# STRWHL-S02-V00-Microcontroller.net
KiCad netlist of a schematic drawn in Altium Designer
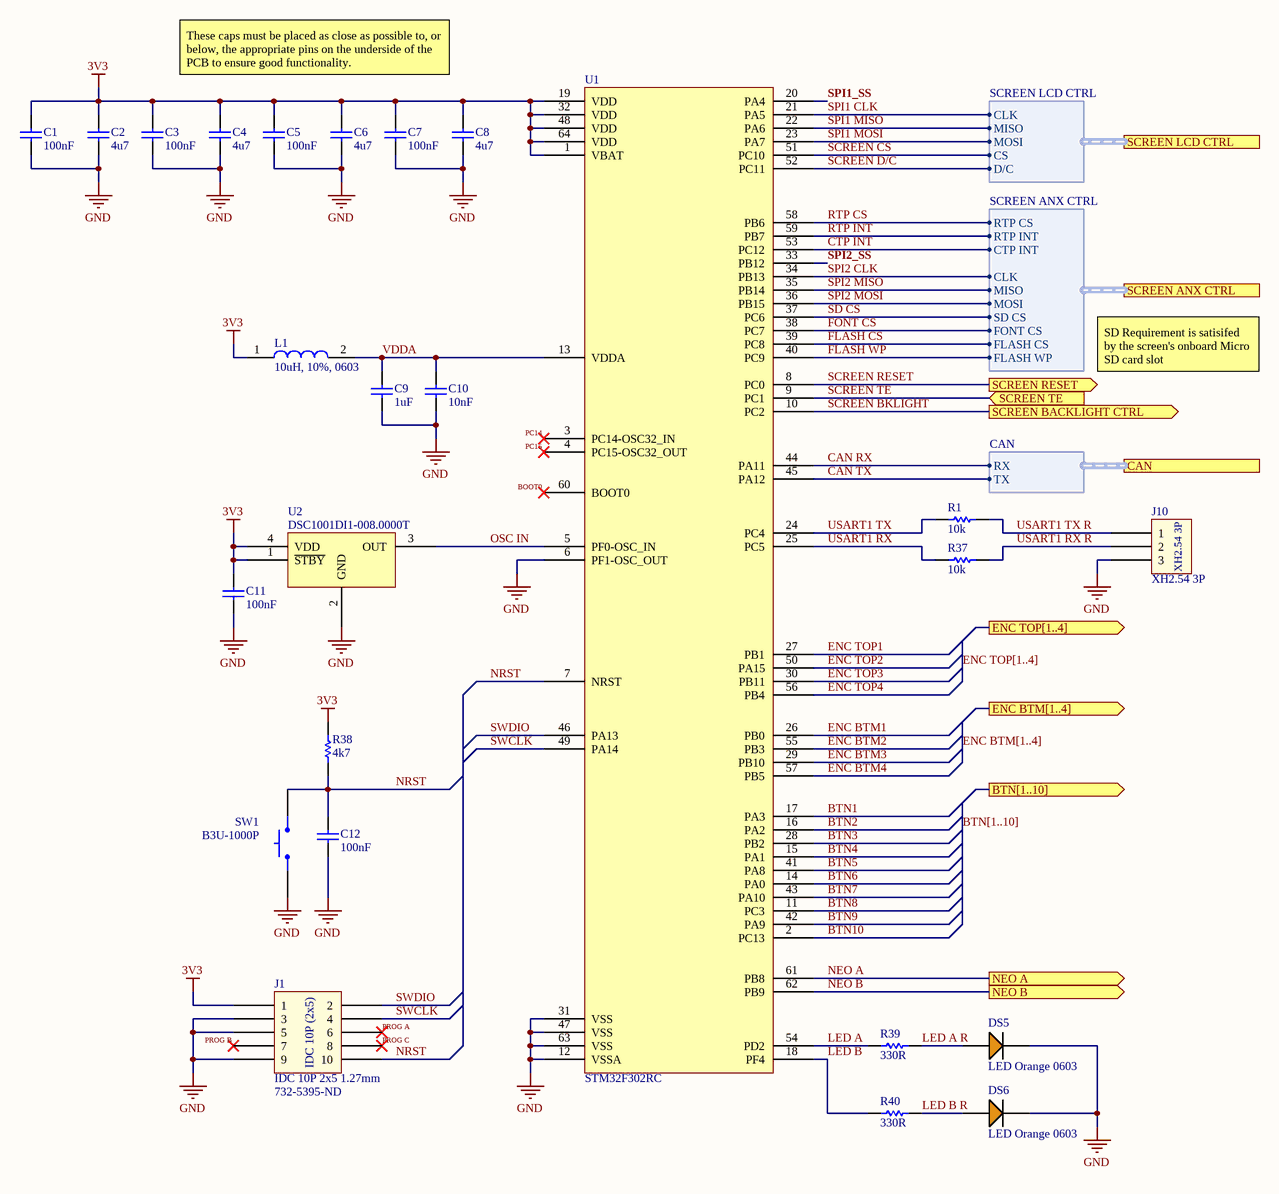
[diagram p0: STRWHL-S02-V00-Microcontroller.SchDoc]

(export (version "E")
  (design (tool "Eeschema 10.0.6"))
  (components
    (comp (ref "C1")
      (value "100nF")
      (footprint "Cap_Ceramic_0603")
      (description "Capacitor, Ceramic, SMD, 100nF, 50V, 5%, X7R, 0603")
      (libsource (lib "StandardCapacitors") (part "100nF 50V 5% X7R 0603"))
    )
    (comp (ref "C2")
      (value "4u7")
      (footprint "Cap_Ceramic_0603")
      (description "Capacitor, Ceramic, SMD, 4u7, 50V, 5%, X7R, 0603")
      (libsource (lib "StandardCapacitors") (part "4u7 50V 5% X7R 0603"))
    )
    (comp (ref "C3")
      (value "100nF")
      (footprint "Cap_Ceramic_0603")
      (description "Capacitor, Ceramic, SMD, 100nF, 50V, 5%, X7R, 0603")
      (libsource (lib "StandardCapacitors") (part "100nF 50V 5% X7R 0603"))
    )
    (comp (ref "C4")
      (value "4u7")
      (footprint "Cap_Ceramic_0603")
      (description "Capacitor, Ceramic, SMD, 4u7, 50V, 5%, X7R, 0603")
      (libsource (lib "StandardCapacitors") (part "4u7 50V 5% X7R 0603"))
    )
    (comp (ref "C5")
      (value "100nF")
      (footprint "Cap_Ceramic_0603")
      (description "Capacitor, Ceramic, SMD, 100nF, 50V, 5%, X7R, 0603")
      (libsource (lib "StandardCapacitors") (part "100nF 50V 5% X7R 0603"))
    )
    (comp (ref "C6")
      (value "4u7")
      (footprint "Cap_Ceramic_0603")
      (description "Capacitor, Ceramic, SMD, 4u7, 50V, 5%, X7R, 0603")
      (libsource (lib "StandardCapacitors") (part "4u7 50V 5% X7R 0603"))
    )
    (comp (ref "C7")
      (value "100nF")
      (footprint "Cap_Ceramic_0603")
      (description "Capacitor, Ceramic, SMD, 100nF, 50V, 5%, X7R, 0603")
      (libsource (lib "StandardCapacitors") (part "100nF 50V 5% X7R 0603"))
    )
    (comp (ref "C8")
      (value "4u7")
      (footprint "Cap_Ceramic_0603")
      (description "Capacitor, Ceramic, SMD, 4u7, 50V, 5%, X7R, 0603")
      (libsource (lib "StandardCapacitors") (part "4u7 50V 5% X7R 0603"))
    )
    (comp (ref "C9")
      (value "1uF")
      (footprint "Cap_Ceramic_0603")
      (description "Capacitor, Ceramic, SMD, 1uF, 25V, 5%, X7R, 0603")
      (libsource (lib "StandardCapacitors") (part "1uF 25V 5% X7R 0603"))
    )
    (comp (ref "C10")
      (value "10nF")
      (footprint "Cap_Ceramic_0603")
      (description "Capacitor, Ceramic, SMD, 10nF, 50V, 5%, X7R, 0603")
      (libsource (lib "StandardCapacitors") (part "10nF 50V 5% X7R 0603"))
    )
    (comp (ref "C11")
      (value "100nF")
      (footprint "Cap_Ceramic_0603")
      (description "Capacitor, Ceramic, SMD, 100nF, 50V, 5%, X7R, 0603")
      (libsource (lib "StandardCapacitors") (part "100nF 50V 5% X7R 0603"))
    )
    (comp (ref "C12")
      (value "100nF")
      (footprint "Cap_Ceramic_0603")
      (description "Capacitor, Ceramic, SMD, 100nF, 50V, 5%, X7R, 0603")
      (libsource (lib "StandardCapacitors") (part "100nF 50V 5% X7R 0603"))
    )
    (comp (ref "DS5")
      (value "LED Orange 0603")
      (footprint "LED ORANGE 0603")
      (libsource (lib "QUTMS_LEDLibrary") (part "LED Orange 0603"))
    )
    (comp (ref "DS6")
      (value "LED Orange 0603")
      (footprint "LED ORANGE 0603")
      (libsource (lib "QUTMS_LEDLibrary") (part "LED Orange 0603"))
    )
    (comp (ref "J1")
      (value "IDC 10P 2x5 1.27mm")
      (footprint "IDC 1.27MM 10P")
      (libsource (lib "IDCConnectors") (part "IDC 10P 2x5 1.27mm"))
    )
    (comp (ref "J10")
      (value "XH2.54 3P")
      (footprint "JST_XH254_3P_TH_RH")
      (libsource (lib "JST_XH254") (part "XH2.54 3P"))
    )
    (comp (ref "L1")
      (value "10uH, 10%, 0603")
      (footprint "Inductor_0603")
      (libsource (lib "QUTMS_InductorLibrary") (part "10uH, 10%, 0603"))
    )
    (comp (ref "R1")
      (value "10k")
      (footprint "Res_ThinFilm_0603")
      (description "Resistor, SMD, 10k, 0.1W, 5%, 0603")
      (libsource (lib "StandardResistors") (part "10k 5% 0603"))
    )
    (comp (ref "R37")
      (value "10k")
      (footprint "Res_ThinFilm_0603")
      (description "Resistor, SMD, 10k, 0.1W, 5%, 0603")
      (libsource (lib "StandardResistors") (part "10k 5% 0603"))
    )
    (comp (ref "R38")
      (value "4k7")
      (footprint "Res_ThinFilm_0603")
      (description "Resistor, SMD, 4k7, 0.1W, 5%, 0603")
      (libsource (lib "StandardResistors") (part "4k7 5% 0603"))
    )
    (comp (ref "R39")
      (value "330R")
      (footprint "Res_ThinFilm_0603")
      (description "Resistor, SMD, 330R, 0.1W, 5%, 0603")
      (libsource (lib "StandardResistors") (part "330R 5% 0603"))
    )
    (comp (ref "R40")
      (value "330R")
      (footprint "Res_ThinFilm_0603")
      (description "Resistor, SMD, 330R, 0.1W, 5%, 0603")
      (libsource (lib "StandardResistors") (part "330R 5% 0603"))
    )
    (comp (ref "SW1")
      (value "B3U-1000P")
      (footprint "BTN B3U-1000P")
      (description "Omron B3U-1000P Ultra Miniture Switch")
      (libsource (lib "QUTMS_SwitchLibrary") (part "BTN B3U-1000P"))
    )
    (comp (ref "U1")
      (value "STM32F302RC")
      (footprint "STM32F302RC")
      (description "ARM® Cortex®-M4 STM32F3 Microcontroller IC 32-Bit 72MHz 256KB (256K x 8) FLASH 64-LQFP (10x10)")
      (libsource (lib "QUTMS_STM32Library") (part "STM32F302RC"))
    )
    (comp (ref "U2")
      (value "DSC1001DI1-008.0000T")
      (footprint "DSC1001DI1-008.0000TCT-ND")
      (description "on 8MHz XO (Standard) CMOS Oscillator 1.8 ~ 3.3V Standby (Power Down) 4-SMD, No Lead")
      (libsource (lib "QUTMS_CrystalLibrary") (part "DSC1001DI1-008.0000T"))
    )
  )
  (nets
    (net (code "6") (name "/BOOT0") (class "Default")
      (node (ref "U1") (pin "60") (pinfunction "BOOT0_60") (pintype "passive+no_connect"))
    )
    (net (code "7") (name "/BTN1") (class "Default")
      (node (ref "U1") (pin "17") (pinfunction "PA3_17") (pintype "passive"))
    )
    (net (code "8") (name "/BTN2") (class "Default")
      (node (ref "U1") (pin "16") (pinfunction "PA2_16") (pintype "passive"))
    )
    (net (code "9") (name "/BTN3") (class "Default")
      (node (ref "U1") (pin "28") (pinfunction "PB2_28") (pintype "passive"))
    )
    (net (code "10") (name "/BTN4") (class "Default")
      (node (ref "U1") (pin "15") (pinfunction "PA1_15") (pintype "passive"))
    )
    (net (code "11") (name "/BTN5") (class "Default")
      (node (ref "U1") (pin "41") (pinfunction "PA8_41") (pintype "passive"))
    )
    (net (code "12") (name "/BTN6") (class "Default")
      (node (ref "U1") (pin "14") (pinfunction "PA0_14") (pintype "passive"))
    )
    (net (code "13") (name "/BTN7") (class "Default")
      (node (ref "U1") (pin "43") (pinfunction "PA10_43") (pintype "passive"))
    )
    (net (code "14") (name "/BTN8") (class "Default")
      (node (ref "U1") (pin "11") (pinfunction "PC3_11") (pintype "passive"))
    )
    (net (code "15") (name "/BTN9") (class "Default")
      (node (ref "U1") (pin "42") (pinfunction "PA9_42") (pintype "passive"))
    )
    (net (code "16") (name "/BTN10") (class "Default")
      (node (ref "U1") (pin "2") (pinfunction "PC13_2") (pintype "passive"))
    )
    (net (code "18") (name "/CAN RX") (class "Default")
      (node (ref "U1") (pin "44") (pinfunction "PA11_44") (pintype "passive"))
    )
    (net (code "19") (name "/CAN TX") (class "Default")
      (node (ref "U1") (pin "45") (pinfunction "PA12_45") (pintype "passive"))
    )
    (net (code "20") (name "/CTP INT") (class "Default")
      (node (ref "U1") (pin "53") (pinfunction "PC12_53") (pintype "passive"))
    )
    (net (code "21") (name "/ENC BTM1") (class "Default")
      (node (ref "U1") (pin "26") (pinfunction "PB0_26") (pintype "passive"))
    )
    (net (code "22") (name "/ENC BTM2") (class "Default")
      (node (ref "U1") (pin "55") (pinfunction "PB3_55") (pintype "passive"))
    )
    (net (code "23") (name "/ENC BTM3") (class "Default")
      (node (ref "U1") (pin "29") (pinfunction "PB10_29") (pintype "passive"))
    )
    (net (code "24") (name "/ENC BTM4") (class "Default")
      (node (ref "U1") (pin "57") (pinfunction "PB5_57") (pintype "passive"))
    )
    (net (code "25") (name "/ENC TOP1") (class "Default")
      (node (ref "U1") (pin "27") (pinfunction "PB1_27") (pintype "passive"))
    )
    (net (code "26") (name "/ENC TOP2") (class "Default")
      (node (ref "U1") (pin "50") (pinfunction "PA15_50") (pintype "passive"))
    )
    (net (code "27") (name "/ENC TOP3") (class "Default")
      (node (ref "U1") (pin "30") (pinfunction "PB11_30") (pintype "passive"))
    )
    (net (code "28") (name "/ENC TOP4") (class "Default")
      (node (ref "U1") (pin "56") (pinfunction "PB4_56") (pintype "passive"))
    )
    (net (code "29") (name "/FLASH CS") (class "Default")
      (node (ref "U1") (pin "39") (pinfunction "PC8_39") (pintype "passive"))
    )
    (net (code "30") (name "/FLASH WP") (class "Default")
      (node (ref "U1") (pin "40") (pinfunction "PC9_40") (pintype "passive"))
    )
    (net (code "31") (name "/FONT CS") (class "Default")
      (node (ref "U1") (pin "38") (pinfunction "PC7_38") (pintype "passive"))
    )
    (net (code "32") (name "/LED A") (class "Default")
      (node (ref "R39") (pin "1") (pinfunction "1_1") (pintype "passive"))
      (node (ref "U1") (pin "54") (pinfunction "PD2_54") (pintype "passive"))
    )
    (net (code "33") (name "/LED A R") (class "Default")
      (node (ref "DS5") (pin "1") (pinfunction "A_1") (pintype "passive"))
      (node (ref "R39") (pin "2") (pinfunction "2_2") (pintype "passive"))
    )
    (net (code "34") (name "/LED B") (class "Default")
      (node (ref "R40") (pin "1") (pinfunction "1_1") (pintype "passive"))
      (node (ref "U1") (pin "18") (pinfunction "PF4_18") (pintype "passive"))
    )
    (net (code "35") (name "/LED B R") (class "Default")
      (node (ref "DS6") (pin "1") (pinfunction "A_1") (pintype "passive"))
      (node (ref "R40") (pin "2") (pinfunction "2_2") (pintype "passive"))
    )
    (net (code "36") (name "/NEO A") (class "Default")
      (node (ref "U1") (pin "61") (pinfunction "PB8_61") (pintype "passive"))
    )
    (net (code "37") (name "/NEO B") (class "Default")
      (node (ref "U1") (pin "62") (pinfunction "PB9_62") (pintype "passive"))
    )
    (net (code "38") (name "/NRST") (class "Default")
      (node (ref "C12") (pin "2") (pinfunction "2_2") (pintype "passive"))
      (node (ref "J1") (pin "10") (pinfunction "10_10") (pintype "passive"))
      (node (ref "R38") (pin "1") (pinfunction "1_1") (pintype "passive"))
      (node (ref "SW1") (pin "2") (pinfunction "2_2") (pintype "passive"))
      (node (ref "U1") (pin "7") (pinfunction "NRST_7") (pintype "passive"))
    )
    (net (code "39") (name "/OSC IN") (class "Default")
      (node (ref "U1") (pin "5") (pinfunction "PF0-OSC_IN_5") (pintype "passive"))
      (node (ref "U2") (pin "3") (pinfunction "OUT_3") (pintype "passive"))
    )
    (net (code "40") (name "/PC14") (class "Default")
      (node (ref "U1") (pin "3") (pinfunction "PC14-OSC32_IN_3") (pintype "passive+no_connect"))
    )
    (net (code "41") (name "/PC15") (class "Default")
      (node (ref "U1") (pin "4") (pinfunction "PC15-OSC32_OUT_4") (pintype "passive+no_connect"))
    )
    (net (code "42") (name "/PROG A") (class "Default")
      (node (ref "J1") (pin "6") (pinfunction "6_6") (pintype "passive+no_connect"))
    )
    (net (code "43") (name "/PROG B") (class "Default")
      (node (ref "J1") (pin "7") (pinfunction "7_7") (pintype "passive+no_connect"))
    )
    (net (code "44") (name "/PROG C") (class "Default")
      (node (ref "J1") (pin "8") (pinfunction "8_8") (pintype "passive+no_connect"))
    )
    (net (code "45") (name "/RTP CS") (class "Default")
      (node (ref "U1") (pin "58") (pinfunction "PB6_58") (pintype "passive"))
    )
    (net (code "46") (name "/RTP INT") (class "Default")
      (node (ref "U1") (pin "59") (pinfunction "PB7_59") (pintype "passive"))
    )
    (net (code "47") (name "/SCREEN BKLIGHT") (class "Default")
      (node (ref "U1") (pin "10") (pinfunction "PC2_10") (pintype "passive"))
    )
    (net (code "48") (name "/SCREEN CS") (class "Default")
      (node (ref "U1") (pin "51") (pinfunction "PC10_51") (pintype "passive"))
    )
    (net (code "49") (name "/SCREEN D{slash}C") (class "Default")
      (node (ref "U1") (pin "52") (pinfunction "PC11_52") (pintype "passive"))
    )
    (net (code "50") (name "/SCREEN RESET") (class "Default")
      (node (ref "U1") (pin "8") (pinfunction "PC0_8") (pintype "passive"))
    )
    (net (code "51") (name "/SCREEN TE") (class "Default")
      (node (ref "U1") (pin "9") (pinfunction "PC1_9") (pintype "passive"))
    )
    (net (code "52") (name "/SD CS") (class "Default")
      (node (ref "U1") (pin "37") (pinfunction "PC6_37") (pintype "passive"))
    )
    (net (code "53") (name "/SPI1 CLK") (class "Default")
      (node (ref "U1") (pin "21") (pinfunction "PA5_21") (pintype "passive"))
    )
    (net (code "54") (name "/SPI1 MISO") (class "Default")
      (node (ref "U1") (pin "22") (pinfunction "PA6_22") (pintype "passive"))
    )
    (net (code "55") (name "/SPI1 MOSI") (class "Default")
      (node (ref "U1") (pin "23") (pinfunction "PA7_23") (pintype "passive"))
    )
    (net (code "56") (name "/SPI1_SS") (class "Default")
      (node (ref "U1") (pin "20") (pinfunction "PA4_20") (pintype "passive"))
    )
    (net (code "57") (name "/SPI2 CLK") (class "Default")
      (node (ref "U1") (pin "34") (pinfunction "PB13_34") (pintype "passive"))
    )
    (net (code "58") (name "/SPI2 MISO") (class "Default")
      (node (ref "U1") (pin "35") (pinfunction "PB14_35") (pintype "passive"))
    )
    (net (code "59") (name "/SPI2 MOSI") (class "Default")
      (node (ref "U1") (pin "36") (pinfunction "PB15_36") (pintype "passive"))
    )
    (net (code "60") (name "/SPI2_SS") (class "Default")
      (node (ref "U1") (pin "33") (pinfunction "PB12_33") (pintype "passive"))
    )
    (net (code "61") (name "/SWCLK") (class "Default")
      (node (ref "J1") (pin "4") (pinfunction "4_4") (pintype "passive"))
      (node (ref "U1") (pin "49") (pinfunction "PA14_49") (pintype "passive"))
    )
    (net (code "62") (name "/SWDIO") (class "Default")
      (node (ref "J1") (pin "2") (pinfunction "2_2") (pintype "passive"))
      (node (ref "U1") (pin "46") (pinfunction "PA13_46") (pintype "passive"))
    )
    (net (code "63") (name "/USART1 RX") (class "Default")
      (node (ref "R37") (pin "1") (pinfunction "1_1") (pintype "passive"))
      (node (ref "U1") (pin "25") (pinfunction "PC5_25") (pintype "passive"))
    )
    (net (code "64") (name "/USART1 RX R") (class "Default")
      (node (ref "J10") (pin "2") (pinfunction "2_2") (pintype "passive"))
      (node (ref "R37") (pin "2") (pinfunction "2_2") (pintype "passive"))
    )
    (net (code "65") (name "/USART1 TX") (class "Default")
      (node (ref "R1") (pin "1") (pinfunction "1_1") (pintype "passive"))
      (node (ref "U1") (pin "24") (pinfunction "PC4_24") (pintype "passive"))
    )
    (net (code "66") (name "/USART1 TX R") (class "Default")
      (node (ref "J10") (pin "1") (pinfunction "1_1") (pintype "passive"))
      (node (ref "R1") (pin "2") (pinfunction "2_2") (pintype "passive"))
    )
    (net (code "67") (name "/VDDA") (class "Default")
      (node (ref "C10") (pin "2") (pinfunction "2_2") (pintype "passive"))
      (node (ref "C9") (pin "2") (pinfunction "2_2") (pintype "passive"))
      (node (ref "L1") (pin "2") (pinfunction "2_2") (pintype "passive"))
      (node (ref "U1") (pin "13") (pinfunction "VDDA_13") (pintype "passive"))
    )
    (net (code "73") (name "3V3") (class "Default")
      (node (ref "C1") (pin "2") (pinfunction "2_2") (pintype "passive"))
      (node (ref "C11") (pin "2") (pinfunction "2_2") (pintype "passive"))
      (node (ref "C2") (pin "2") (pinfunction "2_2") (pintype "passive"))
      (node (ref "C3") (pin "2") (pinfunction "2_2") (pintype "passive"))
      (node (ref "C4") (pin "2") (pinfunction "2_2") (pintype "passive"))
      (node (ref "C5") (pin "2") (pinfunction "2_2") (pintype "passive"))
      (node (ref "C6") (pin "2") (pinfunction "2_2") (pintype "passive"))
      (node (ref "C7") (pin "2") (pinfunction "2_2") (pintype "passive"))
      (node (ref "C8") (pin "2") (pinfunction "2_2") (pintype "passive"))
      (node (ref "J1") (pin "1") (pinfunction "1_1") (pintype "passive"))
      (node (ref "L1") (pin "1") (pinfunction "1_1") (pintype "passive"))
      (node (ref "R38") (pin "2") (pinfunction "2_2") (pintype "passive"))
      (node (ref "U1") (pin "1") (pinfunction "VBAT_1") (pintype "passive"))
      (node (ref "U1") (pin "19") (pinfunction "VDD_19") (pintype "passive"))
      (node (ref "U1") (pin "32") (pinfunction "VDD_32") (pintype "passive"))
      (node (ref "U1") (pin "48") (pinfunction "VDD_48") (pintype "passive"))
      (node (ref "U1") (pin "64") (pinfunction "VDD_64") (pintype "passive"))
      (node (ref "U2") (pin "1") (pinfunction "~{STBY}_1") (pintype "passive"))
      (node (ref "U2") (pin "4") (pinfunction "VDD_4") (pintype "passive"))
    )
    (net (code "74") (name "GND") (class "Default")
      (node (ref "C1") (pin "1") (pinfunction "1_1") (pintype "passive"))
      (node (ref "C10") (pin "1") (pinfunction "1_1") (pintype "passive"))
      (node (ref "C11") (pin "1") (pinfunction "1_1") (pintype "passive"))
      (node (ref "C12") (pin "1") (pinfunction "1_1") (pintype "passive"))
      (node (ref "C2") (pin "1") (pinfunction "1_1") (pintype "passive"))
      (node (ref "C3") (pin "1") (pinfunction "1_1") (pintype "passive"))
      (node (ref "C4") (pin "1") (pinfunction "1_1") (pintype "passive"))
      (node (ref "C5") (pin "1") (pinfunction "1_1") (pintype "passive"))
      (node (ref "C6") (pin "1") (pinfunction "1_1") (pintype "passive"))
      (node (ref "C7") (pin "1") (pinfunction "1_1") (pintype "passive"))
      (node (ref "C8") (pin "1") (pinfunction "1_1") (pintype "passive"))
      (node (ref "C9") (pin "1") (pinfunction "1_1") (pintype "passive"))
      (node (ref "DS5") (pin "2") (pinfunction "C_2") (pintype "passive"))
      (node (ref "DS6") (pin "2") (pinfunction "C_2") (pintype "passive"))
      (node (ref "J1") (pin "3") (pinfunction "3_3") (pintype "passive"))
      (node (ref "J1") (pin "5") (pinfunction "5_5") (pintype "passive"))
      (node (ref "J1") (pin "9") (pinfunction "9_9") (pintype "passive"))
      (node (ref "J10") (pin "3") (pinfunction "3_3") (pintype "passive"))
      (node (ref "SW1") (pin "1") (pinfunction "1_1") (pintype "passive"))
      (node (ref "U1") (pin "12") (pinfunction "VSSA_12") (pintype "passive"))
      (node (ref "U1") (pin "31") (pinfunction "VSS_31") (pintype "passive"))
      (node (ref "U1") (pin "47") (pinfunction "VSS_47") (pintype "passive"))
      (node (ref "U1") (pin "6") (pinfunction "PF1-OSC_OUT_6") (pintype "passive"))
      (node (ref "U1") (pin "63") (pinfunction "VSS_63") (pintype "passive"))
      (node (ref "U2") (pin "2") (pinfunction "GND_2") (pintype "passive"))
    )
  )
)
